# 13_FPGA_PWR.net
KiCad netlist of a schematic drawn in Altium Designer
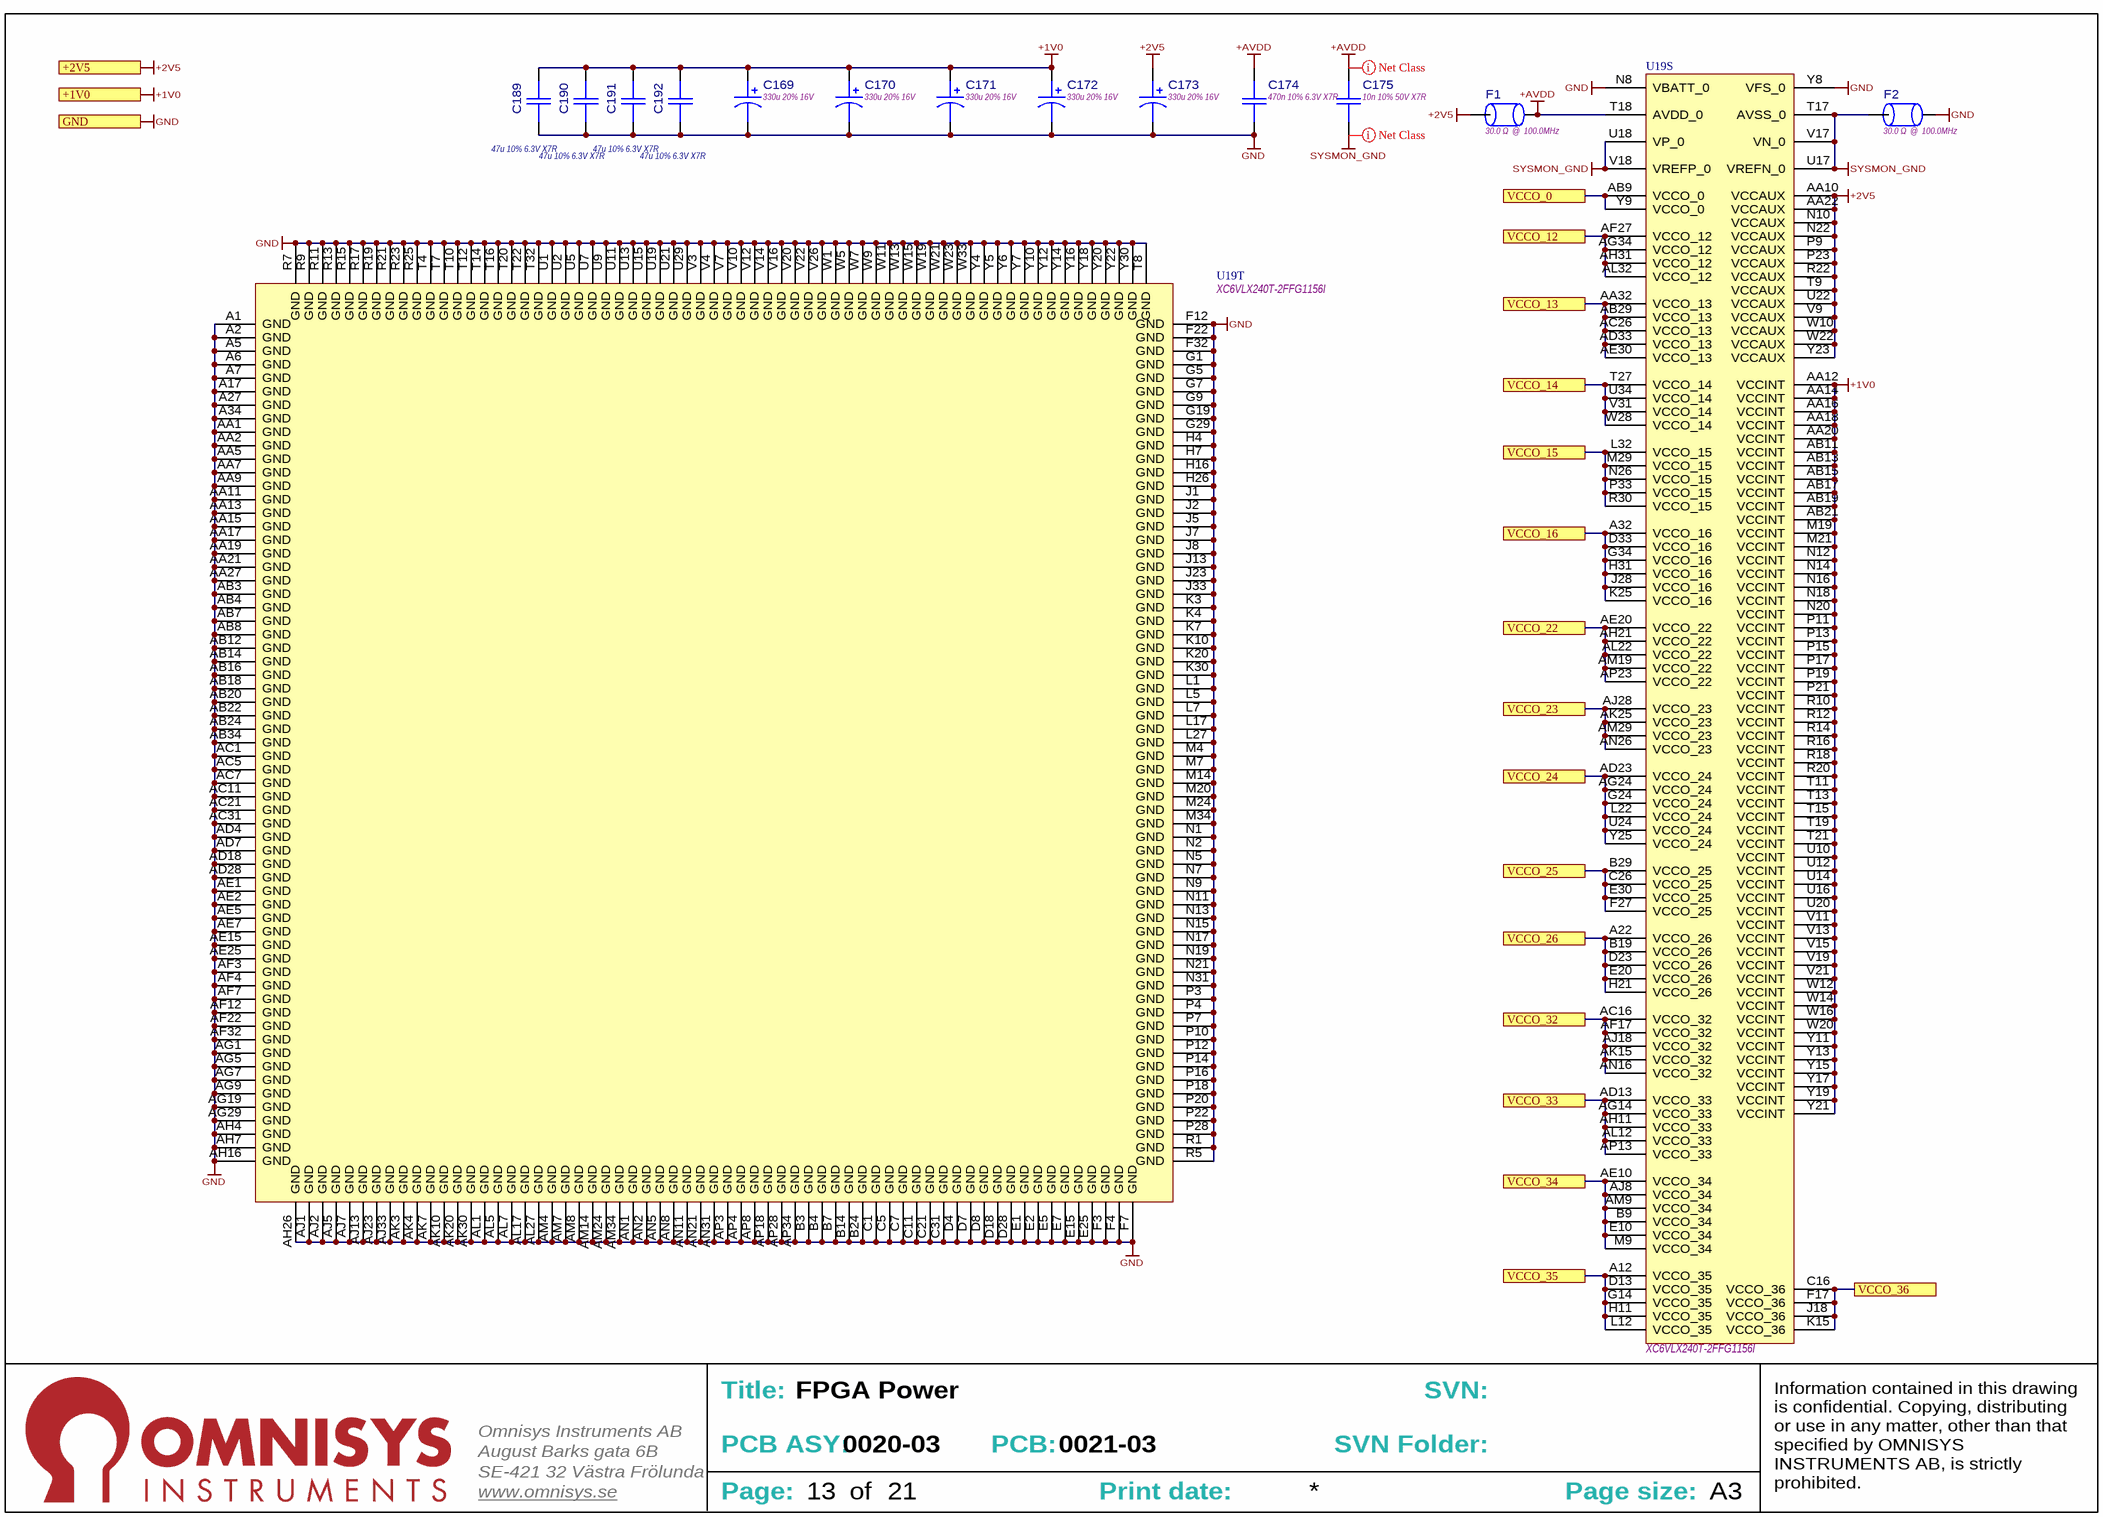
[diagram p0: [13] FPGA_PWR.SchDoc]

(export (version "E")
  (design (tool "Eeschema 10.0.6"))
  (components
    (comp (ref "C169")
      (value "330u 20% 16V")
      (footprint "CAPMP7343X43N")
      (description "Standard tantalum capacitor, 7343/Case E")
      (fields (field (name "TOLERANCE") "20%"))
      (libsource (lib "Omnisys Vault") (part "CAP-2PIN-POL"))
    )
    (comp (ref "C170")
      (value "330u 20% 16V")
      (footprint "CAPMP7343X43N")
      (description "Standard tantalum capacitor, 7343/Case E")
      (fields (field (name "TOLERANCE") "20%"))
      (libsource (lib "Omnisys Vault") (part "CAP-2PIN-POL"))
    )
    (comp (ref "C171")
      (value "330u 20% 16V")
      (footprint "CAPMP7343X43N")
      (description "Standard tantalum capacitor, 7343/Case E")
      (fields (field (name "TOLERANCE") "20%"))
      (libsource (lib "Omnisys Vault") (part "CAP-2PIN-POL"))
    )
    (comp (ref "C172")
      (value "330u 20% 16V")
      (footprint "CAPMP7343X43N")
      (description "Standard tantalum capacitor, 7343/Case E")
      (fields (field (name "TOLERANCE") "20%"))
      (libsource (lib "Omnisys Vault") (part "CAP-2PIN-POL"))
    )
    (comp (ref "C173")
      (value "330u 20% 16V")
      (footprint "CAPMP7343X43N")
      (description "Standard tantalum capacitor, 7343/Case E")
      (fields (field (name "TOLERANCE") "20%"))
      (libsource (lib "Omnisys Vault") (part "CAP-2PIN-POL"))
    )
    (comp (ref "C174")
      (value "470n 10% 6.3V X7R")
      (footprint "CAPC1608X90N")
      (description "Ceramic Chip Capacitor, 0603/1608")
      (fields (field (name "TOLERANCE") "10%"))
      (libsource (lib "Omnisys Vault") (part "CAP-2PIN"))
    )
    (comp (ref "C175")
      (value "10n 10% 50V X7R")
      (footprint "CAPC1608X90N")
      (description "Ceramic Chip Capacitor, 0603/1608")
      (fields (field (name "TOLERANCE") "5%"))
      (libsource (lib "Omnisys Vault") (part "CAP-2PIN"))
    )
    (comp (ref "C189")
      (value "47u 10% 6.3V X7R")
      (footprint "CAPC3225X270N")
      (description "Ceramic Chip Capacitor, 1210/3225")
      (fields (field (name "TOLERANCE") "10%"))
      (libsource (lib "Omnisys Vault") (part "CAP-2PIN"))
    )
    (comp (ref "C190")
      (value "47u 10% 6.3V X7R")
      (footprint "CAPC3225X270N")
      (description "Ceramic Chip Capacitor, 1210/3225")
      (fields (field (name "TOLERANCE") "10%"))
      (libsource (lib "Omnisys Vault") (part "CAP-2PIN"))
    )
    (comp (ref "C191")
      (value "47u 10% 6.3V X7R")
      (footprint "CAPC3225X270N")
      (description "Ceramic Chip Capacitor, 1210/3225")
      (fields (field (name "TOLERANCE") "10%"))
      (libsource (lib "Omnisys Vault") (part "CAP-2PIN"))
    )
    (comp (ref "C192")
      (value "47u 10% 6.3V X7R")
      (footprint "CAPC3225X270N")
      (description "Ceramic Chip Capacitor, 1210/3225")
      (fields (field (name "TOLERANCE") "10%"))
      (libsource (lib "Omnisys Vault") (part "CAP-2PIN"))
    )
    (comp (ref "F1")
      (value "30.0 Ω  @  100.0MHz")
      (footprint "INDC2012X11L")
      (description "Ferrite bead, Würth Elektronik WE-CBF 2012 (0805), 74279206 ,  30.0 Ω  @  100.0MHz")
      (fields (field (name "PARTNUMBER") "74279206"))
      (libsource (lib "Omnisys Vault") (part "BEAD-2PIN"))
    )
    (comp (ref "F2")
      (value "30.0 Ω  @  100.0MHz")
      (footprint "INDC2012X11L")
      (description "Ferrite bead, Würth Elektronik WE-CBF 2012 (0805), 74279206 ,  30.0 Ω  @  100.0MHz")
      (fields (field (name "PARTNUMBER") "74279206"))
      (libsource (lib "Omnisys Vault") (part "BEAD-2PIN"))
    )
    (comp (ref "U19")
      (value "XC6VLX240T-2FFG1156I")
      (footprint "FFG1156")
      (description "FPGA Virtex-6 LXT Family 241152 Cells 40nm (CMOS) Technology 1V 1156-Pin FCBGA")
      (libsource (lib "Omnisys Vault") (part "FPGA-XVR6-XC6VXXXXXT-GA1156"))
    )
  )
  (nets
    (net (code "1") (name "+1V0") (class "Default")
      (node (ref "C169") (pin "1") (pinfunction "1_1") (pintype "passive"))
      (node (ref "C170") (pin "1") (pinfunction "1_1") (pintype "passive"))
      (node (ref "C171") (pin "1") (pinfunction "1_1") (pintype "passive"))
      (node (ref "C172") (pin "1") (pinfunction "1_1") (pintype "passive"))
      (node (ref "C189") (pin "1") (pinfunction "1_1") (pintype "passive"))
      (node (ref "C190") (pin "1") (pinfunction "1_1") (pintype "passive"))
      (node (ref "C191") (pin "1") (pinfunction "1_1") (pintype "passive"))
      (node (ref "C192") (pin "1") (pinfunction "1_1") (pintype "passive"))
      (node (ref "U19") (pin "AA12") (pinfunction "VCCINT_AA12") (pintype "power_in"))
      (node (ref "U19") (pin "AA14") (pinfunction "VCCINT_AA14") (pintype "power_in"))
      (node (ref "U19") (pin "AA16") (pinfunction "VCCINT_AA16") (pintype "power_in"))
      (node (ref "U19") (pin "AA18") (pinfunction "VCCINT_AA18") (pintype "power_in"))
      (node (ref "U19") (pin "AA20") (pinfunction "VCCINT_AA20") (pintype "power_in"))
      (node (ref "U19") (pin "AB11") (pinfunction "VCCINT_AB11") (pintype "power_in"))
      (node (ref "U19") (pin "AB13") (pinfunction "VCCINT_AB13") (pintype "power_in"))
      (node (ref "U19") (pin "AB15") (pinfunction "VCCINT_AB15") (pintype "power_in"))
      (node (ref "U19") (pin "AB17") (pinfunction "VCCINT_AB17") (pintype "power_in"))
      (node (ref "U19") (pin "AB19") (pinfunction "VCCINT_AB19") (pintype "power_in"))
      (node (ref "U19") (pin "AB21") (pinfunction "VCCINT_AB21") (pintype "power_in"))
      (node (ref "U19") (pin "M19") (pinfunction "VCCINT_M19") (pintype "power_in"))
      (node (ref "U19") (pin "M21") (pinfunction "VCCINT_M21") (pintype "power_in"))
      (node (ref "U19") (pin "N12") (pinfunction "VCCINT_N12") (pintype "power_in"))
      (node (ref "U19") (pin "N14") (pinfunction "VCCINT_N14") (pintype "power_in"))
      (node (ref "U19") (pin "N16") (pinfunction "VCCINT_N16") (pintype "power_in"))
      (node (ref "U19") (pin "N18") (pinfunction "VCCINT_N18") (pintype "power_in"))
      (node (ref "U19") (pin "N20") (pinfunction "VCCINT_N20") (pintype "power_in"))
      (node (ref "U19") (pin "P11") (pinfunction "VCCINT_P11") (pintype "power_in"))
      (node (ref "U19") (pin "P13") (pinfunction "VCCINT_P13") (pintype "power_in"))
      (node (ref "U19") (pin "P15") (pinfunction "VCCINT_P15") (pintype "power_in"))
      (node (ref "U19") (pin "P17") (pinfunction "VCCINT_P17") (pintype "power_in"))
      (node (ref "U19") (pin "P19") (pinfunction "VCCINT_P19") (pintype "power_in"))
      (node (ref "U19") (pin "P21") (pinfunction "VCCINT_P21") (pintype "power_in"))
      (node (ref "U19") (pin "R10") (pinfunction "VCCINT_R10") (pintype "power_in"))
      (node (ref "U19") (pin "R12") (pinfunction "VCCINT_R12") (pintype "power_in"))
      (node (ref "U19") (pin "R14") (pinfunction "VCCINT_R14") (pintype "power_in"))
      (node (ref "U19") (pin "R16") (pinfunction "VCCINT_R16") (pintype "power_in"))
      (node (ref "U19") (pin "R18") (pinfunction "VCCINT_R18") (pintype "power_in"))
      (node (ref "U19") (pin "R20") (pinfunction "VCCINT_R20") (pintype "power_in"))
      (node (ref "U19") (pin "T11") (pinfunction "VCCINT_T11") (pintype "power_in"))
      (node (ref "U19") (pin "T13") (pinfunction "VCCINT_T13") (pintype "power_in"))
      (node (ref "U19") (pin "T15") (pinfunction "VCCINT_T15") (pintype "power_in"))
      (node (ref "U19") (pin "T19") (pinfunction "VCCINT_T19") (pintype "power_in"))
      (node (ref "U19") (pin "T21") (pinfunction "VCCINT_T21") (pintype "power_in"))
      (node (ref "U19") (pin "U10") (pinfunction "VCCINT_U10") (pintype "power_in"))
      (node (ref "U19") (pin "U12") (pinfunction "VCCINT_U12") (pintype "power_in"))
      (node (ref "U19") (pin "U14") (pinfunction "VCCINT_U14") (pintype "power_in"))
      (node (ref "U19") (pin "U16") (pinfunction "VCCINT_U16") (pintype "power_in"))
      (node (ref "U19") (pin "U20") (pinfunction "VCCINT_U20") (pintype "power_in"))
      (node (ref "U19") (pin "V11") (pinfunction "VCCINT_V11") (pintype "power_in"))
      (node (ref "U19") (pin "V13") (pinfunction "VCCINT_V13") (pintype "power_in"))
      (node (ref "U19") (pin "V15") (pinfunction "VCCINT_V15") (pintype "power_in"))
      (node (ref "U19") (pin "V19") (pinfunction "VCCINT_V19") (pintype "power_in"))
      (node (ref "U19") (pin "V21") (pinfunction "VCCINT_V21") (pintype "power_in"))
      (node (ref "U19") (pin "W12") (pinfunction "VCCINT_W12") (pintype "power_in"))
      (node (ref "U19") (pin "W14") (pinfunction "VCCINT_W14") (pintype "power_in"))
      (node (ref "U19") (pin "W16") (pinfunction "VCCINT_W16") (pintype "power_in"))
      (node (ref "U19") (pin "W20") (pinfunction "VCCINT_W20") (pintype "power_in"))
      (node (ref "U19") (pin "Y11") (pinfunction "VCCINT_Y11") (pintype "power_in"))
      (node (ref "U19") (pin "Y13") (pinfunction "VCCINT_Y13") (pintype "power_in"))
      (node (ref "U19") (pin "Y15") (pinfunction "VCCINT_Y15") (pintype "power_in"))
      (node (ref "U19") (pin "Y17") (pinfunction "VCCINT_Y17") (pintype "power_in"))
      (node (ref "U19") (pin "Y19") (pinfunction "VCCINT_Y19") (pintype "power_in"))
      (node (ref "U19") (pin "Y21") (pinfunction "VCCINT_Y21") (pintype "power_in"))
    )
    (net (code "2") (name "+2V5") (class "Default")
      (node (ref "C173") (pin "1") (pinfunction "1_1") (pintype "passive"))
      (node (ref "F1") (pin "1") (pinfunction "1_1") (pintype "passive"))
      (node (ref "U19") (pin "AA10") (pinfunction "VCCAUX_AA10") (pintype "power_in"))
      (node (ref "U19") (pin "AA22") (pinfunction "VCCAUX_AA22") (pintype "power_in"))
      (node (ref "U19") (pin "N10") (pinfunction "VCCAUX_N10") (pintype "power_in"))
      (node (ref "U19") (pin "N22") (pinfunction "VCCAUX_N22") (pintype "power_in"))
      (node (ref "U19") (pin "P23") (pinfunction "VCCAUX_P23") (pintype "power_in"))
      (node (ref "U19") (pin "P9") (pinfunction "VCCAUX_P9") (pintype "power_in"))
      (node (ref "U19") (pin "R22") (pinfunction "VCCAUX_R22") (pintype "power_in"))
      (node (ref "U19") (pin "T9") (pinfunction "VCCAUX_T9") (pintype "power_in"))
      (node (ref "U19") (pin "U22") (pinfunction "VCCAUX_U22") (pintype "power_in"))
      (node (ref "U19") (pin "V9") (pinfunction "VCCAUX_V9") (pintype "power_in"))
      (node (ref "U19") (pin "W10") (pinfunction "VCCAUX_W10") (pintype "power_in"))
      (node (ref "U19") (pin "W22") (pinfunction "VCCAUX_W22") (pintype "power_in"))
      (node (ref "U19") (pin "Y23") (pinfunction "VCCAUX_Y23") (pintype "power_in"))
    )
    (net (code "3") (name "+AVDD") (class "Default")
      (node (ref "C174") (pin "1") (pinfunction "1_1") (pintype "passive"))
      (node (ref "C175") (pin "1") (pinfunction "1_1") (pintype "passive"))
      (node (ref "F1") (pin "2") (pinfunction "2_2") (pintype "passive"))
      (node (ref "U19") (pin "T18") (pinfunction "AVDD_0_T18") (pintype "power_in"))
    )
    (net (code "4") (name "/VCCO_0") (class "Default")
      (node (ref "U19") (pin "AB9") (pinfunction "VCCO_0_AB9") (pintype "power_in"))
      (node (ref "U19") (pin "Y9") (pinfunction "VCCO_0_Y9") (pintype "power_in"))
    )
    (net (code "5") (name "/VCCO_12") (class "Default")
      (node (ref "U19") (pin "AF27") (pinfunction "VCCO_12_AF27") (pintype "power_in"))
      (node (ref "U19") (pin "AG34") (pinfunction "VCCO_12_AG34") (pintype "power_in"))
      (node (ref "U19") (pin "AH31") (pinfunction "VCCO_12_AH31") (pintype "power_in"))
      (node (ref "U19") (pin "AL32") (pinfunction "VCCO_12_AL32") (pintype "power_in"))
    )
    (net (code "6") (name "/VCCO_13") (class "Default")
      (node (ref "U19") (pin "AA32") (pinfunction "VCCO_13_AA32") (pintype "power_in"))
      (node (ref "U19") (pin "AB29") (pinfunction "VCCO_13_AB29") (pintype "power_in"))
      (node (ref "U19") (pin "AC26") (pinfunction "VCCO_13_AC26") (pintype "power_in"))
      (node (ref "U19") (pin "AD33") (pinfunction "VCCO_13_AD33") (pintype "power_in"))
      (node (ref "U19") (pin "AE30") (pinfunction "VCCO_13_AE30") (pintype "power_in"))
    )
    (net (code "7") (name "/VCCO_14") (class "Default")
      (node (ref "U19") (pin "T27") (pinfunction "VCCO_14_T27") (pintype "power_in"))
      (node (ref "U19") (pin "U34") (pinfunction "VCCO_14_U34") (pintype "power_in"))
      (node (ref "U19") (pin "V31") (pinfunction "VCCO_14_V31") (pintype "power_in"))
      (node (ref "U19") (pin "W28") (pinfunction "VCCO_14_W28") (pintype "power_in"))
    )
    (net (code "8") (name "/VCCO_15") (class "Default")
      (node (ref "U19") (pin "L32") (pinfunction "VCCO_15_L32") (pintype "power_in"))
      (node (ref "U19") (pin "M29") (pinfunction "VCCO_15_M29") (pintype "power_in"))
      (node (ref "U19") (pin "N26") (pinfunction "VCCO_15_N26") (pintype "power_in"))
      (node (ref "U19") (pin "P33") (pinfunction "VCCO_15_P33") (pintype "power_in"))
      (node (ref "U19") (pin "R30") (pinfunction "VCCO_15_R30") (pintype "power_in"))
    )
    (net (code "9") (name "/VCCO_16") (class "Default")
      (node (ref "U19") (pin "A32") (pinfunction "VCCO_16_A32") (pintype "power_in"))
      (node (ref "U19") (pin "D33") (pinfunction "VCCO_16_D33") (pintype "power_in"))
      (node (ref "U19") (pin "G34") (pinfunction "VCCO_16_G34") (pintype "power_in"))
      (node (ref "U19") (pin "H31") (pinfunction "VCCO_16_H31") (pintype "power_in"))
      (node (ref "U19") (pin "J28") (pinfunction "VCCO_16_J28") (pintype "power_in"))
      (node (ref "U19") (pin "K25") (pinfunction "VCCO_16_K25") (pintype "power_in"))
    )
    (net (code "10") (name "/VCCO_22") (class "Default")
      (node (ref "U19") (pin "AE20") (pinfunction "VCCO_22_AE20") (pintype "power_in"))
      (node (ref "U19") (pin "AH21") (pinfunction "VCCO_22_AH21") (pintype "power_in"))
      (node (ref "U19") (pin "AL22") (pinfunction "VCCO_22_AL22") (pintype "power_in"))
      (node (ref "U19") (pin "AM19") (pinfunction "VCCO_22_AM19") (pintype "power_in"))
      (node (ref "U19") (pin "AP23") (pinfunction "VCCO_22_AP23") (pintype "power_in"))
    )
    (net (code "11") (name "/VCCO_23") (class "Default")
      (node (ref "U19") (pin "AJ28") (pinfunction "VCCO_23_AJ28") (pintype "power_in"))
      (node (ref "U19") (pin "AK25") (pinfunction "VCCO_23_AK25") (pintype "power_in"))
      (node (ref "U19") (pin "AM29") (pinfunction "VCCO_23_AM29") (pintype "power_in"))
      (node (ref "U19") (pin "AN26") (pinfunction "VCCO_23_AN26") (pintype "power_in"))
    )
    (net (code "12") (name "/VCCO_24") (class "Default")
      (node (ref "U19") (pin "AD23") (pinfunction "VCCO_24_AD23") (pintype "power_in"))
      (node (ref "U19") (pin "AG24") (pinfunction "VCCO_24_AG24") (pintype "power_in"))
      (node (ref "U19") (pin "G24") (pinfunction "VCCO_24_G24") (pintype "power_in"))
      (node (ref "U19") (pin "L22") (pinfunction "VCCO_24_L22") (pintype "power_in"))
      (node (ref "U19") (pin "U24") (pinfunction "VCCO_24_U24") (pintype "power_in"))
      (node (ref "U19") (pin "Y25") (pinfunction "VCCO_24_Y25") (pintype "power_in"))
    )
    (net (code "13") (name "/VCCO_25") (class "Default")
      (node (ref "U19") (pin "B29") (pinfunction "VCCO_25_B29") (pintype "power_in"))
      (node (ref "U19") (pin "C26") (pinfunction "VCCO_25_C26") (pintype "power_in"))
      (node (ref "U19") (pin "E30") (pinfunction "VCCO_25_E30") (pintype "power_in"))
      (node (ref "U19") (pin "F27") (pinfunction "VCCO_25_F27") (pintype "power_in"))
    )
    (net (code "14") (name "/VCCO_26") (class "Default")
      (node (ref "U19") (pin "A22") (pinfunction "VCCO_26_A22") (pintype "power_in"))
      (node (ref "U19") (pin "B19") (pinfunction "VCCO_26_B19") (pintype "power_in"))
      (node (ref "U19") (pin "D23") (pinfunction "VCCO_26_D23") (pintype "power_in"))
      (node (ref "U19") (pin "E20") (pinfunction "VCCO_26_E20") (pintype "power_in"))
      (node (ref "U19") (pin "H21") (pinfunction "VCCO_26_H21") (pintype "power_in"))
    )
    (net (code "15") (name "/VCCO_32") (class "Default")
      (node (ref "U19") (pin "AC16") (pinfunction "VCCO_32_AC16") (pintype "power_in"))
      (node (ref "U19") (pin "AF17") (pinfunction "VCCO_32_AF17") (pintype "power_in"))
      (node (ref "U19") (pin "AJ18") (pinfunction "VCCO_32_AJ18") (pintype "power_in"))
      (node (ref "U19") (pin "AK15") (pinfunction "VCCO_32_AK15") (pintype "power_in"))
      (node (ref "U19") (pin "AN16") (pinfunction "VCCO_32_AN16") (pintype "power_in"))
    )
    (net (code "16") (name "/VCCO_33") (class "Default")
      (node (ref "U19") (pin "AD13") (pinfunction "VCCO_33_AD13") (pintype "power_in"))
      (node (ref "U19") (pin "AG14") (pinfunction "VCCO_33_AG14") (pintype "power_in"))
      (node (ref "U19") (pin "AH11") (pinfunction "VCCO_33_AH11") (pintype "power_in"))
      (node (ref "U19") (pin "AL12") (pinfunction "VCCO_33_AL12") (pintype "power_in"))
      (node (ref "U19") (pin "AP13") (pinfunction "VCCO_33_AP13") (pintype "power_in"))
    )
    (net (code "17") (name "/VCCO_34") (class "Default")
      (node (ref "U19") (pin "AE10") (pinfunction "VCCO_34_AE10") (pintype "power_in"))
      (node (ref "U19") (pin "AJ8") (pinfunction "VCCO_34_AJ8") (pintype "power_in"))
      (node (ref "U19") (pin "AM9") (pinfunction "VCCO_34_AM9") (pintype "power_in"))
      (node (ref "U19") (pin "B9") (pinfunction "VCCO_34_B9") (pintype "power_in"))
      (node (ref "U19") (pin "E10") (pinfunction "VCCO_34_E10") (pintype "power_in"))
      (node (ref "U19") (pin "M9") (pinfunction "VCCO_34_M9") (pintype "power_in"))
    )
    (net (code "18") (name "/VCCO_35") (class "Default")
      (node (ref "U19") (pin "A12") (pinfunction "VCCO_35_A12") (pintype "power_in"))
      (node (ref "U19") (pin "D13") (pinfunction "VCCO_35_D13") (pintype "power_in"))
      (node (ref "U19") (pin "G14") (pinfunction "VCCO_35_G14") (pintype "power_in"))
      (node (ref "U19") (pin "H11") (pinfunction "VCCO_35_H11") (pintype "power_in"))
      (node (ref "U19") (pin "L12") (pinfunction "VCCO_35_L12") (pintype "power_in"))
    )
    (net (code "19") (name "/VCCO_36") (class "Default")
      (node (ref "U19") (pin "C16") (pinfunction "VCCO_36_C16") (pintype "power_in"))
      (node (ref "U19") (pin "F17") (pinfunction "VCCO_36_F17") (pintype "power_in"))
      (node (ref "U19") (pin "J18") (pinfunction "VCCO_36_J18") (pintype "power_in"))
      (node (ref "U19") (pin "K15") (pinfunction "VCCO_36_K15") (pintype "power_in"))
    )
    (net (code "20") (name "GND") (class "Default")
      (node (ref "C169") (pin "2") (pinfunction "2_2") (pintype "passive"))
      (node (ref "C170") (pin "2") (pinfunction "2_2") (pintype "passive"))
      (node (ref "C171") (pin "2") (pinfunction "2_2") (pintype "passive"))
      (node (ref "C172") (pin "2") (pinfunction "2_2") (pintype "passive"))
      (node (ref "C173") (pin "2") (pinfunction "2_2") (pintype "passive"))
      (node (ref "C174") (pin "2") (pinfunction "2_2") (pintype "passive"))
      (node (ref "C189") (pin "2") (pinfunction "2_2") (pintype "passive"))
      (node (ref "C190") (pin "2") (pinfunction "2_2") (pintype "passive"))
      (node (ref "C191") (pin "2") (pinfunction "2_2") (pintype "passive"))
      (node (ref "C192") (pin "2") (pinfunction "2_2") (pintype "passive"))
      (node (ref "F2") (pin "2") (pinfunction "2_2") (pintype "passive"))
      (node (ref "U19") (pin "A1") (pinfunction "GND_A1") (pintype "power_in"))
      (node (ref "U19") (pin "A17") (pinfunction "GND_A17") (pintype "power_in"))
      (node (ref "U19") (pin "A2") (pinfunction "GND_A2") (pintype "power_in"))
      (node (ref "U19") (pin "A27") (pinfunction "GND_A27") (pintype "power_in"))
      (node (ref "U19") (pin "A34") (pinfunction "GND_A34") (pintype "power_in"))
      (node (ref "U19") (pin "A5") (pinfunction "GND_A5") (pintype "power_in"))
      (node (ref "U19") (pin "A6") (pinfunction "GND_A6") (pintype "power_in"))
      (node (ref "U19") (pin "A7") (pinfunction "GND_A7") (pintype "power_in"))
      (node (ref "U19") (pin "AA1") (pinfunction "GND_AA1") (pintype "power_in"))
      (node (ref "U19") (pin "AA11") (pinfunction "GND_AA11") (pintype "power_in"))
      (node (ref "U19") (pin "AA13") (pinfunction "GND_AA13") (pintype "power_in"))
      (node (ref "U19") (pin "AA15") (pinfunction "GND_AA15") (pintype "power_in"))
      (node (ref "U19") (pin "AA17") (pinfunction "GND_AA17") (pintype "power_in"))
      (node (ref "U19") (pin "AA19") (pinfunction "GND_AA19") (pintype "power_in"))
      (node (ref "U19") (pin "AA2") (pinfunction "GND_AA2") (pintype "power_in"))
      (node (ref "U19") (pin "AA21") (pinfunction "GND_AA21") (pintype "power_in"))
      (node (ref "U19") (pin "AA27") (pinfunction "GND_AA27") (pintype "power_in"))
      (node (ref "U19") (pin "AA5") (pinfunction "GND_AA5") (pintype "power_in"))
      (node (ref "U19") (pin "AA7") (pinfunction "GND_AA7") (pintype "power_in"))
      (node (ref "U19") (pin "AA9") (pinfunction "GND_AA9") (pintype "power_in"))
      (node (ref "U19") (pin "AB12") (pinfunction "GND_AB12") (pintype "power_in"))
      (node (ref "U19") (pin "AB14") (pinfunction "GND_AB14") (pintype "power_in"))
      (node (ref "U19") (pin "AB16") (pinfunction "GND_AB16") (pintype "power_in"))
      (node (ref "U19") (pin "AB18") (pinfunction "GND_AB18") (pintype "power_in"))
      (node (ref "U19") (pin "AB20") (pinfunction "GND_AB20") (pintype "power_in"))
      (node (ref "U19") (pin "AB22") (pinfunction "GND_AB22") (pintype "power_in"))
      (node (ref "U19") (pin "AB24") (pinfunction "GND_AB24") (pintype "power_in"))
      (node (ref "U19") (pin "AB3") (pinfunction "GND_AB3") (pintype "power_in"))
      (node (ref "U19") (pin "AB34") (pinfunction "GND_AB34") (pintype "power_in"))
      (node (ref "U19") (pin "AB4") (pinfunction "GND_AB4") (pintype "power_in"))
      (node (ref "U19") (pin "AB7") (pinfunction "GND_AB7") (pintype "power_in"))
      (node (ref "U19") (pin "AB8") (pinfunction "GND_AB8") (pintype "power_in"))
      (node (ref "U19") (pin "AC1") (pinfunction "GND_AC1") (pintype "power_in"))
      (node (ref "U19") (pin "AC11") (pinfunction "GND_AC11") (pintype "power_in"))
      (node (ref "U19") (pin "AC21") (pinfunction "GND_AC21") (pintype "power_in"))
      (node (ref "U19") (pin "AC31") (pinfunction "GND_AC31") (pintype "power_in"))
      (node (ref "U19") (pin "AC5") (pinfunction "GND_AC5") (pintype "power_in"))
      (node (ref "U19") (pin "AC7") (pinfunction "GND_AC7") (pintype "power_in"))
      (node (ref "U19") (pin "AD18") (pinfunction "GND_AD18") (pintype "power_in"))
      (node (ref "U19") (pin "AD28") (pinfunction "GND_AD28") (pintype "power_in"))
      (node (ref "U19") (pin "AD4") (pinfunction "GND_AD4") (pintype "power_in"))
      (node (ref "U19") (pin "AD7") (pinfunction "GND_AD7") (pintype "power_in"))
      (node (ref "U19") (pin "AE1") (pinfunction "GND_AE1") (pintype "power_in"))
      (node (ref "U19") (pin "AE15") (pinfunction "GND_AE15") (pintype "power_in"))
      (node (ref "U19") (pin "AE2") (pinfunction "GND_AE2") (pintype "power_in"))
      (node (ref "U19") (pin "AE25") (pinfunction "GND_AE25") (pintype "power_in"))
      (node (ref "U19") (pin "AE5") (pinfunction "GND_AE5") (pintype "power_in"))
      (node (ref "U19") (pin "AE7") (pinfunction "GND_AE7") (pintype "power_in"))
      (node (ref "U19") (pin "AF12") (pinfunction "GND_AF12") (pintype "power_in"))
      (node (ref "U19") (pin "AF22") (pinfunction "GND_AF22") (pintype "power_in"))
      (node (ref "U19") (pin "AF3") (pinfunction "GND_AF3") (pintype "power_in"))
      (node (ref "U19") (pin "AF32") (pinfunction "GND_AF32") (pintype "power_in"))
      (node (ref "U19") (pin "AF4") (pinfunction "GND_AF4") (pintype "power_in"))
      (node (ref "U19") (pin "AF7") (pinfunction "GND_AF7") (pintype "power_in"))
      (node (ref "U19") (pin "AG1") (pinfunction "GND_AG1") (pintype "power_in"))
      (node (ref "U19") (pin "AG19") (pinfunction "GND_AG19") (pintype "power_in"))
      (node (ref "U19") (pin "AG29") (pinfunction "GND_AG29") (pintype "power_in"))
      (node (ref "U19") (pin "AG5") (pinfunction "GND_AG5") (pintype "power_in"))
      (node (ref "U19") (pin "AG7") (pinfunction "GND_AG7") (pintype "power_in"))
      (node (ref "U19") (pin "AG9") (pinfunction "GND_AG9") (pintype "power_in"))
      (node (ref "U19") (pin "AH16") (pinfunction "GND_AH16") (pintype "power_in"))
      (node (ref "U19") (pin "AH26") (pinfunction "GND_AH26") (pintype "power_in"))
      (node (ref "U19") (pin "AH4") (pinfunction "GND_AH4") (pintype "power_in"))
      (node (ref "U19") (pin "AH7") (pinfunction "GND_AH7") (pintype "power_in"))
      (node (ref "U19") (pin "AJ1") (pinfunction "GND_AJ1") (pintype "power_in"))
      (node (ref "U19") (pin "AJ13") (pinfunction "GND_AJ13") (pintype "power_in"))
      (node (ref "U19") (pin "AJ2") (pinfunction "GND_AJ2") (pintype "power_in"))
      (node (ref "U19") (pin "AJ23") (pinfunction "GND_AJ23") (pintype "power_in"))
      (node (ref "U19") (pin "AJ33") (pinfunction "GND_AJ33") (pintype "power_in"))
      (node (ref "U19") (pin "AJ5") (pinfunction "GND_AJ5") (pintype "power_in"))
      (node (ref "U19") (pin "AJ7") (pinfunction "GND_AJ7") (pintype "power_in"))
      (node (ref "U19") (pin "AK10") (pinfunction "GND_AK10") (pintype "power_in"))
      (node (ref "U19") (pin "AK20") (pinfunction "GND_AK20") (pintype "power_in"))
      (node (ref "U19") (pin "AK3") (pinfunction "GND_AK3") (pintype "power_in"))
      (node (ref "U19") (pin "AK30") (pinfunction "GND_AK30") (pintype "power_in"))
      (node (ref "U19") (pin "AK4") (pinfunction "GND_AK4") (pintype "power_in"))
      (node (ref "U19") (pin "AK7") (pinfunction "GND_AK7") (pintype "power_in"))
      (node (ref "U19") (pin "AL1") (pinfunction "GND_AL1") (pintype "power_in"))
      (node (ref "U19") (pin "AL17") (pinfunction "GND_AL17") (pintype "power_in"))
      (node (ref "U19") (pin "AL27") (pinfunction "GND_AL27") (pintype "power_in"))
      (node (ref "U19") (pin "AL5") (pinfunction "GND_AL5") (pintype "power_in"))
      (node (ref "U19") (pin "AL7") (pinfunction "GND_AL7") (pintype "power_in"))
      (node (ref "U19") (pin "AM14") (pinfunction "GND_AM14") (pintype "power_in"))
      (node (ref "U19") (pin "AM24") (pinfunction "GND_AM24") (pintype "power_in"))
      (node (ref "U19") (pin "AM34") (pinfunction "GND_AM34") (pintype "power_in"))
      (node (ref "U19") (pin "AM4") (pinfunction "GND_AM4") (pintype "power_in"))
      (node (ref "U19") (pin "AM7") (pinfunction "GND_AM7") (pintype "power_in"))
      (node (ref "U19") (pin "AM8") (pinfunction "GND_AM8") (pintype "power_in"))
      (node (ref "U19") (pin "AN1") (pinfunction "GND_AN1") (pintype "power_in"))
      (node (ref "U19") (pin "AN11") (pinfunction "GND_AN11") (pintype "power_in"))
      (node (ref "U19") (pin "AN2") (pinfunction "GND_AN2") (pintype "power_in"))
      (node (ref "U19") (pin "AN21") (pinfunction "GND_AN21") (pintype "power_in"))
      (node (ref "U19") (pin "AN31") (pinfunction "GND_AN31") (pintype "power_in"))
      (node (ref "U19") (pin "AN5") (pinfunction "GND_AN5") (pintype "power_in"))
      (node (ref "U19") (pin "AN8") (pinfunction "GND_AN8") (pintype "power_in"))
      (node (ref "U19") (pin "AP18") (pinfunction "GND_AP18") (pintype "power_in"))
      (node (ref "U19") (pin "AP28") (pinfunction "GND_AP28") (pintype "power_in"))
      (node (ref "U19") (pin "AP3") (pinfunction "GND_AP3") (pintype "power_in"))
      (node (ref "U19") (pin "AP34") (pinfunction "GND_AP34") (pintype "power_in"))
      (node (ref "U19") (pin "AP4") (pinfunction "GND_AP4") (pintype "power_in"))
      (node (ref "U19") (pin "AP8") (pinfunction "GND_AP8") (pintype "power_in"))
      (node (ref "U19") (pin "B14") (pinfunction "GND_B14") (pintype "power_in"))
      (node (ref "U19") (pin "B24") (pinfunction "GND_B24") (pintype "power_in"))
      (node (ref "U19") (pin "B3") (pinfunction "GND_B3") (pintype "power_in"))
      (node (ref "U19") (pin "B4") (pinfunction "GND_B4") (pintype "power_in"))
      (node (ref "U19") (pin "B7") (pinfunction "GND_B7") (pintype "power_in"))
      (node (ref "U19") (pin "C1") (pinfunction "GND_C1") (pintype "power_in"))
      (node (ref "U19") (pin "C11") (pinfunction "GND_C11") (pintype "power_in"))
      (node (ref "U19") (pin "C21") (pinfunction "GND_C21") (pintype "power_in"))
      (node (ref "U19") (pin "C31") (pinfunction "GND_C31") (pintype "power_in"))
      (node (ref "U19") (pin "C5") (pinfunction "GND_C5") (pintype "power_in"))
      (node (ref "U19") (pin "C7") (pinfunction "GND_C7") (pintype "power_in"))
      (node (ref "U19") (pin "D18") (pinfunction "GND_D18") (pintype "power_in"))
      (node (ref "U19") (pin "D28") (pinfunction "GND_D28") (pintype "power_in"))
      (node (ref "U19") (pin "D4") (pinfunction "GND_D4") (pintype "power_in"))
      (node (ref "U19") (pin "D7") (pinfunction "GND_D7") (pintype "power_in"))
      (node (ref "U19") (pin "D8") (pinfunction "GND_D8") (pintype "power_in"))
      (node (ref "U19") (pin "E1") (pinfunction "GND_E1") (pintype "power_in"))
      (node (ref "U19") (pin "E15") (pinfunction "GND_E15") (pintype "power_in"))
      (node (ref "U19") (pin "E2") (pinfunction "GND_E2") (pintype "power_in"))
      (node (ref "U19") (pin "E25") (pinfunction "GND_E25") (pintype "power_in"))
      (node (ref "U19") (pin "E5") (pinfunction "GND_E5") (pintype "power_in"))
      (node (ref "U19") (pin "E7") (pinfunction "GND_E7") (pintype "power_in"))
      (node (ref "U19") (pin "F12") (pinfunction "GND_F12") (pintype "power_in"))
      (node (ref "U19") (pin "F22") (pinfunction "GND_F22") (pintype "power_in"))
      (node (ref "U19") (pin "F3") (pinfunction "GND_F3") (pintype "power_in"))
      (node (ref "U19") (pin "F32") (pinfunction "GND_F32") (pintype "power_in"))
      (node (ref "U19") (pin "F4") (pinfunction "GND_F4") (pintype "power_in"))
      (node (ref "U19") (pin "F7") (pinfunction "GND_F7") (pintype "power_in"))
      (node (ref "U19") (pin "G1") (pinfunction "GND_G1") (pintype "power_in"))
      (node (ref "U19") (pin "G19") (pinfunction "GND_G19") (pintype "power_in"))
      (node (ref "U19") (pin "G29") (pinfunction "GND_G29") (pintype "power_in"))
      (node (ref "U19") (pin "G5") (pinfunction "GND_G5") (pintype "power_in"))
      (node (ref "U19") (pin "G7") (pinfunction "GND_G7") (pintype "power_in"))
      (node (ref "U19") (pin "G9") (pinfunction "GND_G9") (pintype "power_in"))
      (node (ref "U19") (pin "H16") (pinfunction "GND_H16") (pintype "power_in"))
      (node (ref "U19") (pin "H26") (pinfunction "GND_H26") (pintype "power_in"))
      (node (ref "U19") (pin "H4") (pinfunction "GND_H4") (pintype "power_in"))
      (node (ref "U19") (pin "H7") (pinfunction "GND_H7") (pintype "power_in"))
      (node (ref "U19") (pin "J1") (pinfunction "GND_J1") (pintype "power_in"))
      (node (ref "U19") (pin "J13") (pinfunction "GND_J13") (pintype "power_in"))
      (node (ref "U19") (pin "J2") (pinfunction "GND_J2") (pintype "power_in"))
      (node (ref "U19") (pin "J23") (pinfunction "GND_J23") (pintype "power_in"))
      (node (ref "U19") (pin "J33") (pinfunction "GND_J33") (pintype "power_in"))
      (node (ref "U19") (pin "J5") (pinfunction "GND_J5") (pintype "power_in"))
      (node (ref "U19") (pin "J7") (pinfunction "GND_J7") (pintype "power_in"))
      (node (ref "U19") (pin "J8") (pinfunction "GND_J8") (pintype "power_in"))
      (node (ref "U19") (pin "K10") (pinfunction "GND_K10") (pintype "power_in"))
      (node (ref "U19") (pin "K20") (pinfunction "GND_K20") (pintype "power_in"))
      (node (ref "U19") (pin "K3") (pinfunction "GND_K3") (pintype "power_in"))
      (node (ref "U19") (pin "K30") (pinfunction "GND_K30") (pintype "power_in"))
      (node (ref "U19") (pin "K4") (pinfunction "GND_K4") (pintype "power_in"))
      (node (ref "U19") (pin "K7") (pinfunction "GND_K7") (pintype "power_in"))
      (node (ref "U19") (pin "L1") (pinfunction "GND_L1") (pintype "power_in"))
      (node (ref "U19") (pin "L17") (pinfunction "GND_L17") (pintype "power_in"))
      (node (ref "U19") (pin "L27") (pinfunction "GND_L27") (pintype "power_in"))
      (node (ref "U19") (pin "L5") (pinfunction "GND_L5") (pintype "power_in"))
      (node (ref "U19") (pin "L7") (pinfunction "GND_L7") (pintype "power_in"))
      (node (ref "U19") (pin "M14") (pinfunction "GND_M14") (pintype "power_in"))
      (node (ref "U19") (pin "M20") (pinfunction "GND_M20") (pintype "power_in"))
      (node (ref "U19") (pin "M24") (pinfunction "GND_M24") (pintype "power_in"))
      (node (ref "U19") (pin "M34") (pinfunction "GND_M34") (pintype "power_in"))
      (node (ref "U19") (pin "M4") (pinfunction "GND_M4") (pintype "power_in"))
      (node (ref "U19") (pin "M7") (pinfunction "GND_M7") (pintype "power_in"))
      (node (ref "U19") (pin "N1") (pinfunction "GND_N1") (pintype "power_in"))
      (node (ref "U19") (pin "N11") (pinfunction "GND_N11") (pintype "power_in"))
      (node (ref "U19") (pin "N13") (pinfunction "GND_N13") (pintype "power_in"))
      (node (ref "U19") (pin "N15") (pinfunction "GND_N15") (pintype "power_in"))
      (node (ref "U19") (pin "N17") (pinfunction "GND_N17") (pintype "power_in"))
      (node (ref "U19") (pin "N19") (pinfunction "GND_N19") (pintype "power_in"))
      (node (ref "U19") (pin "N2") (pinfunction "GND_N2") (pintype "power_in"))
      (node (ref "U19") (pin "N21") (pinfunction "GND_N21") (pintype "power_in"))
      (node (ref "U19") (pin "N31") (pinfunction "GND_N31") (pintype "power_in"))
      (node (ref "U19") (pin "N5") (pinfunction "GND_N5") (pintype "power_in"))
      (node (ref "U19") (pin "N7") (pinfunction "GND_N7") (pintype "power_in"))
      (node (ref "U19") (pin "N8") (pinfunction "VBATT_0_N8") (pintype "power_in"))
      (node (ref "U19") (pin "N9") (pinfunction "GND_N9") (pintype "power_in"))
      (node (ref "U19") (pin "P10") (pinfunction "GND_P10") (pintype "power_in"))
      (node (ref "U19") (pin "P12") (pinfunction "GND_P12") (pintype "power_in"))
      (node (ref "U19") (pin "P14") (pinfunction "GND_P14") (pintype "power_in"))
      (node (ref "U19") (pin "P16") (pinfunction "GND_P16") (pintype "power_in"))
      (node (ref "U19") (pin "P18") (pinfunction "GND_P18") (pintype "power_in"))
      (node (ref "U19") (pin "P20") (pinfunction "GND_P20") (pintype "power_in"))
      (node (ref "U19") (pin "P22") (pinfunction "GND_P22") (pintype "power_in"))
      (node (ref "U19") (pin "P28") (pinfunction "GND_P28") (pintype "power_in"))
      (node (ref "U19") (pin "P3") (pinfunction "GND_P3") (pintype "power_in"))
      (node (ref "U19") (pin "P4") (pinfunction "GND_P4") (pintype "power_in"))
      (node (ref "U19") (pin "P7") (pinfunction "GND_P7") (pintype "power_in"))
      (node (ref "U19") (pin "R1") (pinfunction "GND_R1") (pintype "power_in"))
      (node (ref "U19") (pin "R11") (pinfunction "GND_R11") (pintype "power_in"))
      (node (ref "U19") (pin "R13") (pinfunction "GND_R13") (pintype "power_in"))
      (node (ref "U19") (pin "R15") (pinfunction "GND_R15") (pintype "power_in"))
      (node (ref "U19") (pin "R17") (pinfunction "GND_R17") (pintype "power_in"))
      (node (ref "U19") (pin "R19") (pinfunction "GND_R19") (pintype "power_in"))
      (node (ref "U19") (pin "R21") (pinfunction "GND_R21") (pintype "power_in"))
      (node (ref "U19") (pin "R23") (pinfunction "GND_R23") (pintype "power_in"))
      (node (ref "U19") (pin "R25") (pinfunction "GND_R25") (pintype "power_in"))
      (node (ref "U19") (pin "R5") (pinfunction "GND_R5") (pintype "power_in"))
      (node (ref "U19") (pin "R7") (pinfunction "GND_R7") (pintype "power_in"))
      (node (ref "U19") (pin "R9") (pinfunction "GND_R9") (pintype "power_in"))
      (node (ref "U19") (pin "T10") (pinfunction "GND_T10") (pintype "power_in"))
      (node (ref "U19") (pin "T12") (pinfunction "GND_T12") (pintype "power_in"))
      (node (ref "U19") (pin "T14") (pinfunction "GND_T14") (pintype "power_in"))
      (node (ref "U19") (pin "T16") (pinfunction "GND_T16") (pintype "power_in"))
      (node (ref "U19") (pin "T20") (pinfunction "GND_T20") (pintype "power_in"))
      (node (ref "U19") (pin "T22") (pinfunction "GND_T22") (pintype "power_in"))
      (node (ref "U19") (pin "T32") (pinfunction "GND_T32") (pintype "power_in"))
      (node (ref "U19") (pin "T4") (pinfunction "GND_T4") (pintype "power_in"))
      (node (ref "U19") (pin "T7") (pinfunction "GND_T7") (pintype "power_in"))
      (node (ref "U19") (pin "T8") (pinfunction "GND_T8") (pintype "power_in"))
      (node (ref "U19") (pin "U1") (pinfunction "GND_U1") (pintype "power_in"))
      (node (ref "U19") (pin "U11") (pinfunction "GND_U11") (pintype "power_in"))
      (node (ref "U19") (pin "U13") (pinfunction "GND_U13") (pintype "power_in"))
      (node (ref "U19") (pin "U15") (pinfunction "GND_U15") (pintype "power_in"))
      (node (ref "U19") (pin "U19") (pinfunction "GND_U19") (pintype "power_in"))
      (node (ref "U19") (pin "U2") (pinfunction "GND_U2") (pintype "power_in"))
      (node (ref "U19") (pin "U21") (pinfunction "GND_U21") (pintype "power_in"))
      (node (ref "U19") (pin "U29") (pinfunction "GND_U29") (pintype "power_in"))
      (node (ref "U19") (pin "U5") (pinfunction "GND_U5") (pintype "power_in"))
      (node (ref "U19") (pin "U7") (pinfunction "GND_U7") (pintype "power_in"))
      (node (ref "U19") (pin "U9") (pinfunction "GND_U9") (pintype "power_in"))
      (node (ref "U19") (pin "V10") (pinfunction "GND_V10") (pintype "power_in"))
      (node (ref "U19") (pin "V12") (pinfunction "GND_V12") (pintype "power_in"))
      (node (ref "U19") (pin "V14") (pinfunction "GND_V14") (pintype "power_in"))
      (node (ref "U19") (pin "V16") (pinfunction "GND_V16") (pintype "power_in"))
      (node (ref "U19") (pin "V20") (pinfunction "GND_V20") (pintype "power_in"))
      (node (ref "U19") (pin "V22") (pinfunction "GND_V22") (pintype "power_in"))
      (node (ref "U19") (pin "V26") (pinfunction "GND_V26") (pintype "power_in"))
      (node (ref "U19") (pin "V3") (pinfunction "GND_V3") (pintype "power_in"))
      (node (ref "U19") (pin "V4") (pinfunction "GND_V4") (pintype "power_in"))
      (node (ref "U19") (pin "V7") (pinfunction "GND_V7") (pintype "power_in"))
      (node (ref "U19") (pin "W1") (pinfunction "GND_W1") (pintype "power_in"))
      (node (ref "U19") (pin "W11") (pinfunction "GND_W11") (pintype "power_in"))
      (node (ref "U19") (pin "W13") (pinfunction "GND_W13") (pintype "power_in"))
      (node (ref "U19") (pin "W15") (pinfunction "GND_W15") (pintype "power_in"))
      (node (ref "U19") (pin "W19") (pinfunction "GND_W19") (pintype "power_in"))
      (node (ref "U19") (pin "W21") (pinfunction "GND_W21") (pintype "power_in"))
      (node (ref "U19") (pin "W23") (pinfunction "GND_W23") (pintype "power_in"))
      (node (ref "U19") (pin "W33") (pinfunction "GND_W33") (pintype "power_in"))
      (node (ref "U19") (pin "W5") (pinfunction "GND_W5") (pintype "power_in"))
      (node (ref "U19") (pin "W7") (pinfunction "GND_W7") (pintype "power_in"))
      (node (ref "U19") (pin "W9") (pinfunction "GND_W9") (pintype "power_in"))
      (node (ref "U19") (pin "Y10") (pinfunction "GND_Y10") (pintype "power_in"))
      (node (ref "U19") (pin "Y12") (pinfunction "GND_Y12") (pintype "power_in"))
      (node (ref "U19") (pin "Y14") (pinfunction "GND_Y14") (pintype "power_in"))
      (node (ref "U19") (pin "Y16") (pinfunction "GND_Y16") (pintype "power_in"))
      (node (ref "U19") (pin "Y18") (pinfunction "GND_Y18") (pintype "power_in"))
      (node (ref "U19") (pin "Y20") (pinfunction "GND_Y20") (pintype "power_in"))
      (node (ref "U19") (pin "Y22") (pinfunction "GND_Y22") (pintype "power_in"))
      (node (ref "U19") (pin "Y30") (pinfunction "GND_Y30") (pintype "power_in"))
      (node (ref "U19") (pin "Y4") (pinfunction "GND_Y4") (pintype "power_in"))
      (node (ref "U19") (pin "Y5") (pinfunction "GND_Y5") (pintype "power_in"))
      (node (ref "U19") (pin "Y6") (pinfunction "GND_Y6") (pintype "power_in"))
      (node (ref "U19") (pin "Y7") (pinfunction "GND_Y7") (pintype "power_in"))
      (node (ref "U19") (pin "Y8") (pinfunction "VFS_0_Y8") (pintype "power_in"))
    )
    (net (code "21") (name "SYSMON_GND") (class "Default")
      (node (ref "C175") (pin "2") (pinfunction "2_2") (pintype "passive"))
      (node (ref "F2") (pin "1") (pinfunction "1_1") (pintype "passive"))
      (node (ref "U19") (pin "T17") (pinfunction "AVSS_0_T17") (pintype "power_in"))
      (node (ref "U19") (pin "U17") (pinfunction "VREFN_0_U17") (pintype "power_in"))
      (node (ref "U19") (pin "U18") (pinfunction "VP_0_U18") (pintype "power_in"))
      (node (ref "U19") (pin "V17") (pinfunction "VN_0_V17") (pintype "power_in"))
      (node (ref "U19") (pin "V18") (pinfunction "VREFP_0_V18") (pintype "power_in"))
    )
  )
)
